# nano-addon-schematic.net
KiCad netlist of a schematic drawn in EAGLE
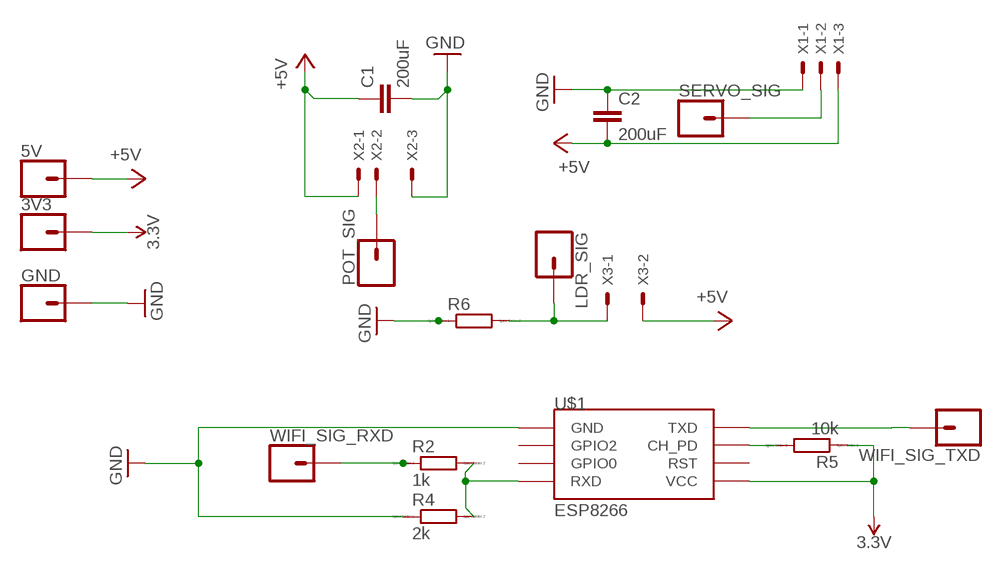
[diagram p0: schematic, sheet 1]

(export (version "E")
  (design (tool "Eeschema 10.0.6"))
  (components
    (comp (ref "3V3")
      (value "CONN_01")
      (footprint "eagle-import:1X01")
      (libsource (lib "eagle-import") (part "CONN_01"))
    )
    (comp (ref "5V")
      (value "CONN_01")
      (footprint "eagle-import:1X01")
      (libsource (lib "eagle-import") (part "CONN_01"))
    )
    (comp (ref "C1")
      (value "200uF")
      (footprint "eagle-import:C050-030X075")
      (libsource (lib "eagle-import") (part "C-EU050-030X075"))
    )
    (comp (ref "C2")
      (value "200uF")
      (footprint "eagle-import:C050-030X075")
      (libsource (lib "eagle-import") (part "C-EU050-030X075"))
    )
    (comp (ref "GND")
      (value "CONN_01")
      (footprint "eagle-import:1X01")
      (libsource (lib "eagle-import") (part "CONN_01"))
    )
    (comp (ref "LDR_SIG")
      (value "CONN_01")
      (footprint "eagle-import:1X01")
      (libsource (lib "eagle-import") (part "CONN_01"))
    )
    (comp (ref "POT_SIG")
      (value "CONN_01")
      (footprint "eagle-import:1X01")
      (libsource (lib "eagle-import") (part "CONN_01"))
    )
    (comp (ref "R2")
      (value "1k")
      (footprint "eagle-import:0204_7")
      (libsource (lib "eagle-import") (part "R0204/7"))
    )
    (comp (ref "R4")
      (value "2k")
      (footprint "eagle-import:0204_7")
      (libsource (lib "eagle-import") (part "R0204/7"))
    )
    (comp (ref "R5")
      (value "10k")
      (footprint "eagle-import:0204_7")
      (libsource (lib "eagle-import") (part "R0204/7"))
    )
    (comp (ref "R6")
      (value "R0204/7")
      (footprint "eagle-import:0204_7")
      (libsource (lib "eagle-import") (part "R0204/7"))
    )
    (comp (ref "SERVO_SIG")
      (value "CONN_01")
      (footprint "eagle-import:1X01")
      (libsource (lib "eagle-import") (part "CONN_01"))
    )
    (comp (ref "U$1")
      (value "ESP8266")
      (footprint "eagle-import:ESP01")
      (libsource (lib "eagle-import") (part "ESP01"))
    )
    (comp (ref "WIFI_SIG_RXD")
      (value "CONN_01")
      (footprint "eagle-import:1X01")
      (libsource (lib "eagle-import") (part "CONN_01"))
    )
    (comp (ref "WIFI_SIG_TXD")
      (value "CONN_01")
      (footprint "eagle-import:1X01")
      (libsource (lib "eagle-import") (part "CONN_01"))
    )
    (comp (ref "X1")
      (value "KK-156-3")
      (footprint "eagle-import:KK-156-3")
      (fields (field (name "MF") "MOLEX"))
      (libsource (lib "eagle-import") (part "KK-156-3"))
    )
    (comp (ref "X2")
      (value "KK-156-3")
      (footprint "eagle-import:KK-156-3")
      (fields (field (name "MF") "MOLEX"))
      (libsource (lib "eagle-import") (part "KK-156-3"))
    )
    (comp (ref "X3")
      (value "KK-156-2")
      (footprint "eagle-import:KK-156-2")
      (fields (field (name "MF") "MOLEX"))
      (libsource (lib "eagle-import") (part "KK-156-2"))
    )
  )
  (nets
    (net (code "1") (name "+5V") (class "Default")
      (node (ref "5V") (pin "1") (pinfunction "1_1") (pintype "passive"))
      (node (ref "C1") (pin "1") (pinfunction "1_1") (pintype "passive"))
      (node (ref "C2") (pin "2") (pinfunction "2_2") (pintype "passive"))
      (node (ref "X1") (pin "3") (pinfunction "S_3") (pintype "passive"))
      (node (ref "X2") (pin "1") (pinfunction "S_1") (pintype "passive"))
      (node (ref "X3") (pin "2") (pinfunction "S_2") (pintype "passive"))
    )
    (net (code "2") (name "3.3V") (class "Default")
      (node (ref "3V3") (pin "1") (pinfunction "1_1") (pintype "passive"))
      (node (ref "R5") (pin "1") (pinfunction "1_1") (pintype "passive"))
      (node (ref "U$1") (pin "VCC") (pinfunction "VCC_VCC") (pintype "bidirectional"))
    )
    (net (code "3") (name "GND") (class "Default")
      (node (ref "C1") (pin "2") (pinfunction "2_2") (pintype "passive"))
      (node (ref "C2") (pin "1") (pinfunction "1_1") (pintype "passive"))
      (node (ref "GND") (pin "1") (pinfunction "1_1") (pintype "passive"))
      (node (ref "R4") (pin "1") (pinfunction "1_1") (pintype "passive"))
      (node (ref "R6") (pin "1") (pinfunction "1_1") (pintype "passive"))
      (node (ref "U$1") (pin "GND") (pinfunction "GND_GND") (pintype "bidirectional"))
      (node (ref "X1") (pin "1") (pinfunction "S_1") (pintype "passive"))
      (node (ref "X2") (pin "3") (pinfunction "S_3") (pintype "passive"))
    )
    (net (code "4") (name "Net-(R2-Pad1)") (class "Default")
      (node (ref "R2") (pin "1") (pinfunction "1_1") (pintype "passive"))
      (node (ref "WIFI_SIG_RXD") (pin "1") (pinfunction "1_1") (pintype "passive"))
    )
    (net (code "5") (name "Net-(R5-Pad2)") (class "Default")
      (node (ref "R5") (pin "2") (pinfunction "2_2") (pintype "passive"))
      (node (ref "U$1") (pin "CH_PD") (pinfunction "CH_PD_CH_PD") (pintype "bidirectional"))
    )
    (net (code "6") (name "Net-(U$1-RXD)") (class "Default")
      (node (ref "R2") (pin "2") (pinfunction "2_2") (pintype "passive"))
      (node (ref "R4") (pin "2") (pinfunction "2_2") (pintype "passive"))
      (node (ref "U$1") (pin "RX") (pinfunction "RXD_RX") (pintype "bidirectional"))
    )
    (net (code "7") (name "Net-(U$1-TXD)") (class "Default")
      (node (ref "U$1") (pin "TX") (pinfunction "TXD_TX") (pintype "bidirectional"))
      (node (ref "WIFI_SIG_TXD") (pin "1") (pinfunction "1_1") (pintype "passive"))
    )
    (net (code "8") (name "Net-(X1B-S)") (class "Default")
      (node (ref "SERVO_SIG") (pin "1") (pinfunction "1_1") (pintype "passive"))
      (node (ref "X1") (pin "2") (pinfunction "S_2") (pintype "passive"))
    )
    (net (code "9") (name "Net-(X2B-S)") (class "Default")
      (node (ref "POT_SIG") (pin "1") (pinfunction "1_1") (pintype "passive"))
      (node (ref "X2") (pin "2") (pinfunction "S_2") (pintype "passive"))
    )
    (net (code "10") (name "Net-(X3A-S)") (class "Default")
      (node (ref "LDR_SIG") (pin "1") (pinfunction "1_1") (pintype "passive"))
      (node (ref "R6") (pin "2") (pinfunction "2_2") (pintype "passive"))
      (node (ref "X3") (pin "1") (pinfunction "S_1") (pintype "passive"))
    )
    (net (code "11") (name "unconnected-(U$1-PadGPIO0)") (class "Default")
      (node (ref "U$1") (pin "GPIO0") (pinfunction "GPIO0_GPIO0") (pintype "bidirectional"))
    )
    (net (code "12") (name "unconnected-(U$1-PadGPIO2)") (class "Default")
      (node (ref "U$1") (pin "GPIO2") (pinfunction "GPIO2_GPIO2") (pintype "bidirectional"))
    )
    (net (code "13") (name "unconnected-(U$1-PadRST)") (class "Default")
      (node (ref "U$1") (pin "RST") (pinfunction "RST_RST") (pintype "bidirectional"))
    )
  )
)
